# Photodiode.net
KiCad netlist of a schematic drawn in Altium Designer
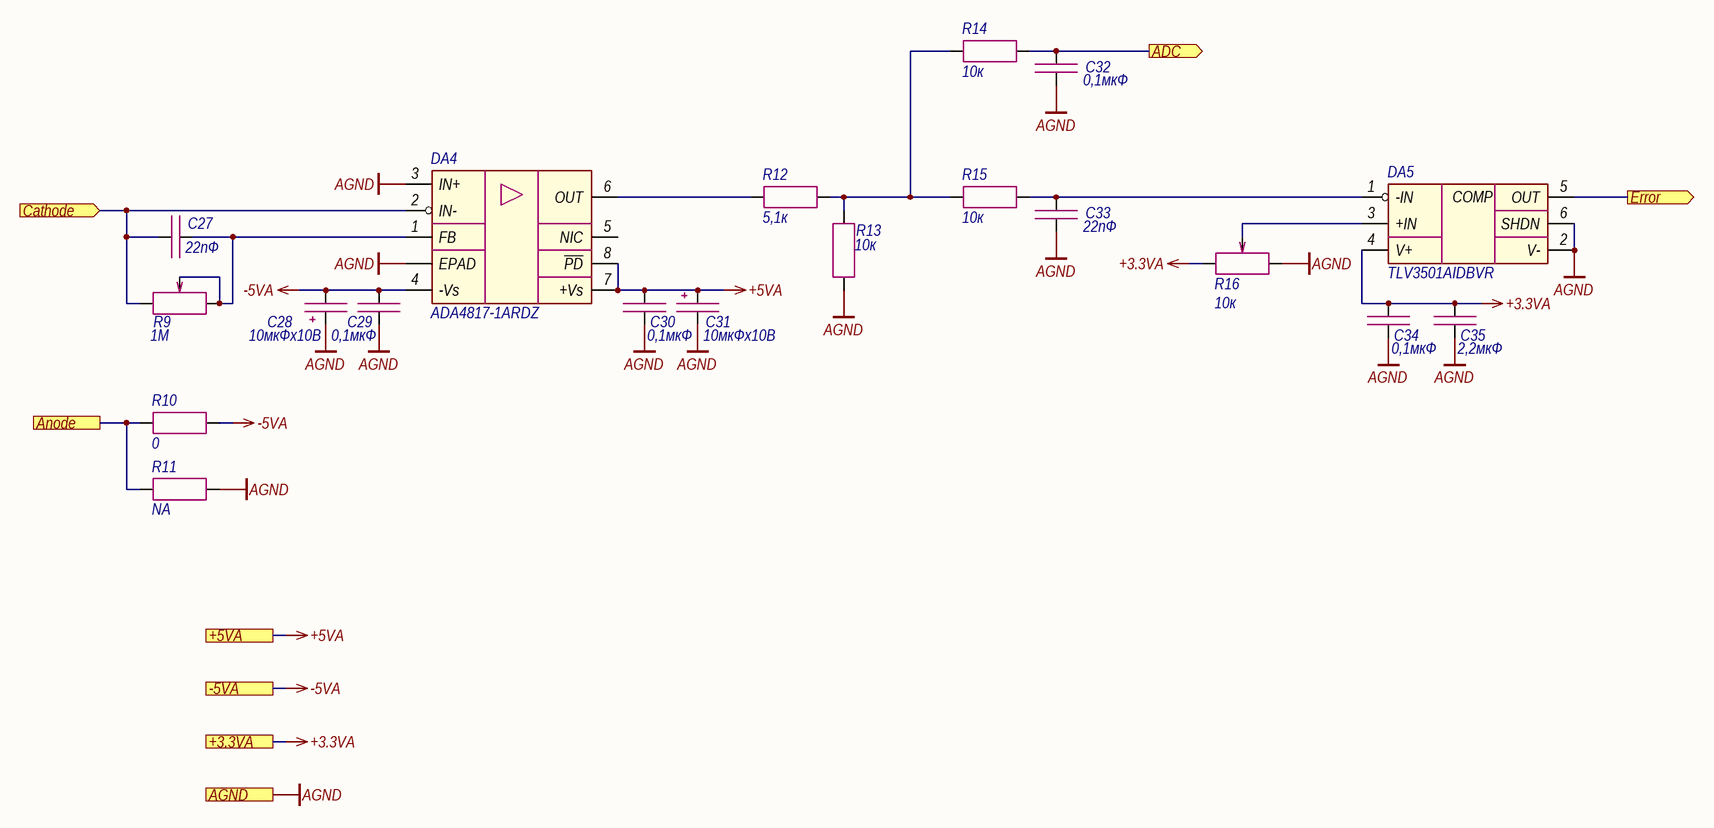
[diagram p0: Photodiode.SchDoc]

(export (version "E")
  (design (tool "Eeschema 10.0.6"))
  (components
    (comp (ref "C27")
      (value "22пФ")
      (footprint "Pcb_library:CAP_0603")
      (fields (field (name "MANUFACTURER") "Murata"))
      (libsource (lib "Schem_library") (part "Capacitor"))
    )
    (comp (ref "C28")
      (value "10мкФх10B")
      (footprint "Pcb_library:CAP_A")
      (libsource (lib "Schem_library") (part "Capacitor_Polar"))
    )
    (comp (ref "C29")
      (value "0,1мкФ")
      (footprint "Pcb_library:CAP_0603")
      (fields (field (name "MANUFACTURER") "Murata"))
      (libsource (lib "Schem_library") (part "Capacitor"))
    )
    (comp (ref "C30")
      (value "0,1мкФ")
      (footprint "Pcb_library:CAP_0603")
      (fields (field (name "MANUFACTURER") "Murata"))
      (libsource (lib "Schem_library") (part "Capacitor"))
    )
    (comp (ref "C31")
      (value "10мкФх10B")
      (footprint "Pcb_library:CAP_A")
      (libsource (lib "Schem_library") (part "Capacitor_Polar"))
    )
    (comp (ref "C32")
      (value "0,1мкФ")
      (footprint "Pcb_library:CAP_0603")
      (fields (field (name "MANUFACTURER") "Murata"))
      (libsource (lib "Schem_library") (part "Capacitor"))
    )
    (comp (ref "C33")
      (value "22пФ")
      (footprint "Pcb_library:CAP_0603")
      (fields (field (name "MANUFACTURER") "Murata"))
      (libsource (lib "Schem_library") (part "Capacitor"))
    )
    (comp (ref "C34")
      (value "0,1мкФ")
      (footprint "Pcb_library:CAP_0603")
      (fields (field (name "MANUFACTURER") "Murata"))
      (libsource (lib "Schem_library") (part "Capacitor"))
    )
    (comp (ref "C35")
      (value "2,2мкФ")
      (footprint "Pcb_library:CAP_0603")
      (fields (field (name "MANUFACTURER") "Murata"))
      (libsource (lib "Schem_library") (part "Capacitor"))
    )
    (comp (ref "DA4")
      (value "ADA4817-1ARDZ")
      (footprint "Pcb_library:SOIC-8 EPAD")
      (fields (field (name "MANUFACTURER") "Analog Devices"))
      (libsource (lib "Schem_library") (part "ADA4817-1ARDZ"))
    )
    (comp (ref "DA5")
      (value "TLV3501AIDBVR")
      (footprint "Pcb_library:SOT-23-6")
      (fields (field (name "MANUFACTURER") "Texas Instruments"))
      (libsource (lib "Schem_library") (part "TLV3501"))
    )
    (comp (ref "R9")
      (value "1М")
      (footprint "Pcb_library:3224W")
      (fields (field (name "MANUFACTURER") "Bourns"))
      (libsource (lib "Schem_library") (part "Resistor_Variable"))
    )
    (comp (ref "R10")
      (value "0")
      (footprint "Pcb_library:RES_0603")
      (fields (field (name "MANUFACTURER") "Yageo"))
      (libsource (lib "Schem_library") (part "Resistor"))
    )
    (comp (ref "R11")
      (value "NA")
      (footprint "Pcb_library:RES_0603")
      (libsource (lib "Schem_library") (part "Resistor"))
    )
    (comp (ref "R12")
      (value "5,1к")
      (footprint "Pcb_library:RES_0603")
      (fields (field (name "MANUFACTURER") "Yageo"))
      (libsource (lib "Schem_library") (part "Resistor"))
    )
    (comp (ref "R13")
      (value "10к")
      (footprint "Pcb_library:RES_0603")
      (fields (field (name "MANUFACTURER") "Yageo"))
      (libsource (lib "Schem_library") (part "Resistor"))
    )
    (comp (ref "R14")
      (value "10к")
      (footprint "Pcb_library:RES_0603")
      (fields (field (name "MANUFACTURER") "Yageo"))
      (libsource (lib "Schem_library") (part "Resistor"))
    )
    (comp (ref "R15")
      (value "10к")
      (footprint "Pcb_library:RES_0603")
      (fields (field (name "MANUFACTURER") "Yageo"))
      (libsource (lib "Schem_library") (part "Resistor"))
    )
    (comp (ref "R16")
      (value "10к")
      (footprint "Pcb_library:3224W")
      (fields (field (name "MANUFACTURER") "Bourns"))
      (libsource (lib "Schem_library") (part "Resistor_Variable"))
    )
  )
  (nets
    (net (code "1") (name "+3.3VA") (class "Default")
      (node (ref "C34") (pin "1") (pinfunction "1_1") (pintype "passive"))
      (node (ref "C35") (pin "1") (pinfunction "1_1") (pintype "passive"))
      (node (ref "DA5") (pin "4") (pinfunction "V+_4") (pintype "passive"))
      (node (ref "R16") (pin "3") (pintype "passive"))
    )
    (net (code "2") (name "+5VA") (class "Default")
      (node (ref "C30") (pin "1") (pinfunction "1_1") (pintype "passive"))
      (node (ref "C31") (pin "1") (pinfunction "1_1") (pintype "passive"))
      (node (ref "DA4") (pin "7") (pinfunction "+Vs_7") (pintype "passive"))
      (node (ref "DA4") (pin "8") (pinfunction "~{PD}_8") (pintype "passive"))
    )
    (net (code "3") (name "-5VA") (class "Default")
      (node (ref "C28") (pin "2") (pinfunction "2_2") (pintype "passive"))
      (node (ref "C29") (pin "1") (pinfunction "1_1") (pintype "passive"))
      (node (ref "DA4") (pin "4") (pinfunction "-Vs_4") (pintype "passive"))
      (node (ref "R10") (pin "1") (pinfunction "1_1") (pintype "passive"))
    )
    (net (code "4") (name "/ADC") (class "Default")
      (node (ref "C32") (pin "1") (pinfunction "1_1") (pintype "passive"))
      (node (ref "R14") (pin "2") (pinfunction "2_2") (pintype "passive"))
    )
    (net (code "5") (name "/Anode") (class "Default")
      (node (ref "R10") (pin "2") (pinfunction "2_2") (pintype "passive"))
      (node (ref "R11") (pin "1") (pinfunction "1_1") (pintype "passive"))
    )
    (net (code "6") (name "/Cathode") (class "Default")
      (node (ref "C27") (pin "2") (pinfunction "2_2") (pintype "passive"))
      (node (ref "DA4") (pin "2") (pinfunction "IN-_2") (pintype "passive"))
      (node (ref "R9") (pin "1") (pintype "passive"))
    )
    (net (code "7") (name "/Error") (class "Default")
      (node (ref "DA5") (pin "5") (pinfunction "OUT_5") (pintype "passive"))
    )
    (net (code "8") (name "AGND") (class "Default")
      (node (ref "C28") (pin "1") (pinfunction "1_1") (pintype "passive"))
      (node (ref "C29") (pin "2") (pinfunction "2_2") (pintype "passive"))
      (node (ref "C30") (pin "2") (pinfunction "2_2") (pintype "passive"))
      (node (ref "C31") (pin "2") (pinfunction "2_2") (pintype "passive"))
      (node (ref "C32") (pin "2") (pinfunction "2_2") (pintype "passive"))
      (node (ref "C33") (pin "2") (pinfunction "2_2") (pintype "passive"))
      (node (ref "C34") (pin "2") (pinfunction "2_2") (pintype "passive"))
      (node (ref "C35") (pin "2") (pinfunction "2_2") (pintype "passive"))
      (node (ref "DA4") (pin "3") (pinfunction "IN+_3") (pintype "passive"))
      (node (ref "DA4") (pin "EPAD") (pinfunction "EPAD_EPAD") (pintype "passive"))
      (node (ref "DA5") (pin "2") (pinfunction "V-_2") (pintype "passive"))
      (node (ref "DA5") (pin "6") (pinfunction "SHDN_6") (pintype "passive"))
      (node (ref "R11") (pin "2") (pinfunction "2_2") (pintype "passive"))
      (node (ref "R13") (pin "2") (pinfunction "2_2") (pintype "passive"))
      (node (ref "R16") (pin "1") (pintype "passive"))
    )
    (net (code "9") (name "Net-(DA4-FB)") (class "Default")
      (node (ref "C27") (pin "1") (pinfunction "1_1") (pintype "passive"))
      (node (ref "DA4") (pin "1") (pinfunction "FB_1") (pintype "passive"))
      (node (ref "R9") (pin "2") (pintype "passive"))
      (node (ref "R9") (pin "3") (pintype "passive"))
    )
    (net (code "10") (name "Net-(DA4-OUT)") (class "Default")
      (node (ref "DA4") (pin "6") (pinfunction "OUT_6") (pintype "passive"))
      (node (ref "R12") (pin "1") (pinfunction "1_1") (pintype "passive"))
    )
    (net (code "11") (name "Net-(DA5-+IN)") (class "Default")
      (node (ref "DA5") (pin "3") (pinfunction "+IN_3") (pintype "passive"))
      (node (ref "R16") (pin "2") (pintype "passive"))
    )
    (net (code "12") (name "Net-(DA5--IN)") (class "Default")
      (node (ref "C33") (pin "1") (pinfunction "1_1") (pintype "passive"))
      (node (ref "DA5") (pin "1") (pinfunction "-IN_1") (pintype "passive"))
      (node (ref "R15") (pin "2") (pinfunction "2_2") (pintype "passive"))
    )
    (net (code "13") (name "Net-(R12-Pad2)") (class "Default")
      (node (ref "R12") (pin "2") (pinfunction "2_2") (pintype "passive"))
      (node (ref "R13") (pin "1") (pinfunction "1_1") (pintype "passive"))
      (node (ref "R14") (pin "1") (pinfunction "1_1") (pintype "passive"))
      (node (ref "R15") (pin "1") (pinfunction "1_1") (pintype "passive"))
    )
    (net (code "14") (name "unconnected-(DA4-NIC-Pad5)") (class "Default")
      (node (ref "DA4") (pin "5") (pinfunction "NIC_5") (pintype "passive"))
    )
  )
)
